# Clock_Extension.net
KiCad netlist of a schematic drawn in EAGLE
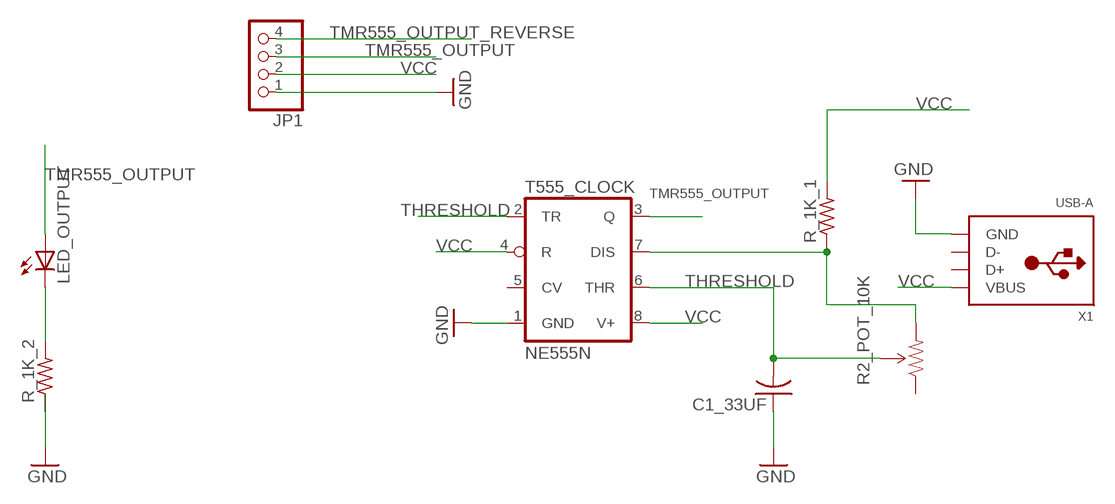
[diagram p0: schematic, sheet 1]

(export (version "E")
  (design (tool "Eeschema 10.0.6"))
  (components
    (comp (ref "C1_33UF")
      (value "C-US025-030X050")
      (footprint "eagle-import:C025-030X050")
      (libsource (lib "eagle-import") (part "C-US025-030X050"))
    )
    (comp (ref "JP1")
      (value "PINHD-1X4")
      (footprint "eagle-import:1X04")
      (libsource (lib "eagle-import") (part "PINHD-1X4"))
    )
    (comp (ref "LED_OUTPUT")
      (value "LEDSMT1206")
      (footprint "eagle-import:1206")
      (libsource (lib "eagle-import") (part "LEDSMT1206"))
    )
    (comp (ref "R2_POT_10K")
      (value "TRIMPOTPTH")
      (footprint "eagle-import:TRIM_POT_PTH")
      (libsource (lib "eagle-import") (part "TRIMPOTPTH"))
    )
    (comp (ref "R_1K_1")
      (value "R-US_R1206")
      (footprint "eagle-import:R1206")
      (libsource (lib "eagle-import") (part "R-US_R1206"))
    )
    (comp (ref "R_1K_2")
      (value "R-US_R1206")
      (footprint "eagle-import:R1206")
      (libsource (lib "eagle-import") (part "R-US_R1206"))
    )
    (comp (ref "T555_CLOCK")
      (value "NE555N")
      (footprint "eagle-import:DIL08")
      (libsource (lib "eagle-import") (part "555NNE"))
    )
    (comp (ref "X1")
      (value "USB-A")
      (footprint "eagle-import:MOLEX_480371000")
      (libsource (lib "eagle-import") (part "USB-A"))
    )
  )
  (nets
    (net (code "1") (name "/THRESHOLD") (class "Default")
      (node (ref "C1_33UF") (pin "2") (pinfunction "2_2") (pintype "passive"))
      (node (ref "R2_POT_10K") (pin "2") (pinfunction "WIPER_2") (pintype "passive"))
      (node (ref "T555_CLOCK") (pin "2") (pinfunction "TR_2") (pintype "input"))
      (node (ref "T555_CLOCK") (pin "6") (pinfunction "THR_6") (pintype "input"))
    )
    (net (code "2") (name "/TMR555_OUTPUT") (class "Default")
      (node (ref "JP1") (pin "3") (pinfunction "3_3") (pintype "passive"))
      (node (ref "LED_OUTPUT") (pin "A") (pinfunction "A_A") (pintype "passive"))
      (node (ref "T555_CLOCK") (pin "3") (pinfunction "Q_3") (pintype "output"))
    )
    (net (code "3") (name "/TMR555_OUTPUT_REVERSE") (class "Default")
      (node (ref "JP1") (pin "4") (pinfunction "4_4") (pintype "passive"))
    )
    (net (code "4") (name "/VCC") (class "Default")
      (node (ref "JP1") (pin "2") (pinfunction "2_2") (pintype "passive"))
      (node (ref "R_1K_1") (pin "2") (pinfunction "2_2") (pintype "passive"))
      (node (ref "T555_CLOCK") (pin "4") (pinfunction "R_4") (pintype "input"))
      (node (ref "T555_CLOCK") (pin "8") (pinfunction "V+_8") (pintype "power_in"))
      (node (ref "X1") (pin "1") (pinfunction "VBUS_1") (pintype "power_in"))
    )
    (net (code "5") (name "GND") (class "Default")
      (node (ref "C1_33UF") (pin "1") (pinfunction "1_1") (pintype "passive"))
      (node (ref "JP1") (pin "1") (pinfunction "1_1") (pintype "passive"))
      (node (ref "R_1K_2") (pin "1") (pinfunction "1_1") (pintype "passive"))
      (node (ref "T555_CLOCK") (pin "1") (pinfunction "GND_1") (pintype "power_in"))
      (node (ref "X1") (pin "4") (pinfunction "GND_4") (pintype "power_in"))
    )
    (net (code "6") (name "Net-(LED_OUTPUT-PadC)") (class "Default")
      (node (ref "LED_OUTPUT") (pin "C") (pinfunction "C_C") (pintype "passive"))
      (node (ref "R_1K_2") (pin "2") (pinfunction "2_2") (pintype "passive"))
    )
    (net (code "7") (name "Net-(R2_POT_10K-CW)") (class "Default")
      (node (ref "R2_POT_10K") (pin "3") (pinfunction "CW_3") (pintype "passive"))
      (node (ref "R_1K_1") (pin "1") (pinfunction "1_1") (pintype "passive"))
      (node (ref "T555_CLOCK") (pin "7") (pinfunction "DIS_7") (pintype "input"))
    )
    (net (code "8") (name "unconnected-(R2_POT_10K-CCW-Pad1)") (class "Default")
      (node (ref "R2_POT_10K") (pin "1") (pinfunction "CCW_1") (pintype "passive"))
    )
    (net (code "9") (name "unconnected-(T555_CLOCK-CV-Pad5)") (class "Default")
      (node (ref "T555_CLOCK") (pin "5") (pinfunction "CV_5") (pintype "input"))
    )
    (net (code "10") (name "unconnected-(X1-D+-Pad3)") (class "Default")
      (node (ref "X1") (pin "3") (pinfunction "D+_3") (pintype "bidirectional"))
    )
    (net (code "11") (name "unconnected-(X1-D--Pad2)") (class "Default")
      (node (ref "X1") (pin "2") (pinfunction "D-_2") (pintype "bidirectional"))
    )
  )
)
